# JIANGYA.net
KiCad netlist of a schematic drawn in Altium Designer
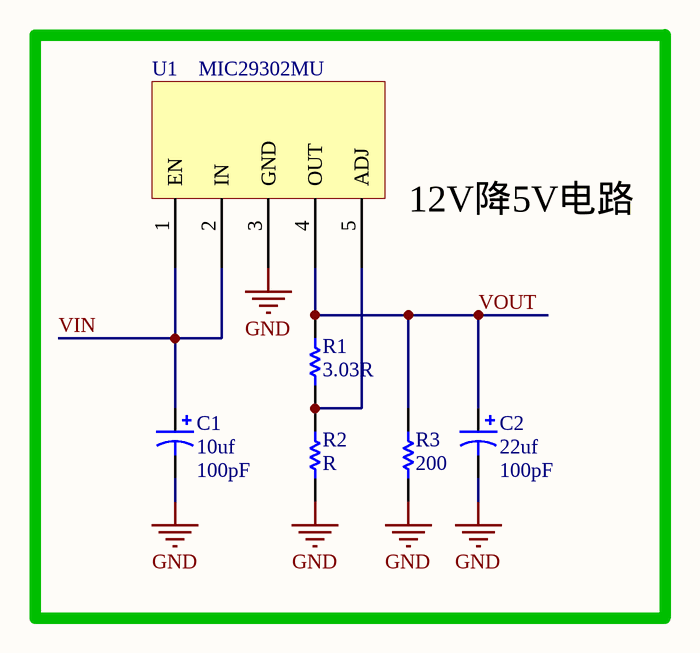
[diagram p0: JIANGYA.SchDoc]

(export (version "E")
  (design (tool "Eeschema 10.0.6"))
  (components
    (comp (ref "C1")
      (value "10uf")
      (footprint "RB7.6-15")
      (description "Polarized Capacitor (Radial)")
      (fields (field (name "ALTIUM_VALUE") "100pF") (field (name "PUBLISHER") "Altium Limited"))
      (libsource (lib "Miscellaneous Devices") (part "Cap Pol1"))
    )
    (comp (ref "C2")
      (value "22uf")
      (footprint "RB7.6-15")
      (description "Polarized Capacitor (Radial)")
      (fields (field (name "ALTIUM_VALUE") "100pF") (field (name "PUBLISHER") "Altium Limited"))
      (libsource (lib "Miscellaneous Devices") (part "Cap Pol1"))
    )
    (comp (ref "R1")
      (value "3.03R")
      (footprint "AXIAL-0.3")
      (description "Resistor")
      (fields (field (name "PUBLISHER") "Altium Limited"))
      (libsource (lib "Miscellaneous Devices") (part "Res1"))
    )
    (comp (ref "R2")
      (value "R")
      (footprint "AXIAL-0.3")
      (description "Resistor")
      (fields (field (name "PUBLISHER") "Altium Limited"))
      (libsource (lib "Miscellaneous Devices") (part "Res1"))
    )
    (comp (ref "R3")
      (value "200")
      (footprint "AXIAL-0.3")
      (description "Resistor")
      (fields (field (name "PUBLISHER") "Altium Limited"))
      (libsource (lib "Miscellaneous Devices") (part "Res1"))
    )
    (comp (ref "U1")
      (value "MIC29302MU")
      (footprint "TO263-5")
      (libsource (lib "TO263-5") (part "Component_1"))
    )
  )
  (nets
    (net (code "1") (name "/VIN") (class "Default")
      (node (ref "C1") (pin "1") (pinfunction "1_1") (pintype "passive"))
      (node (ref "U1") (pin "1") (pinfunction "EN_1") (pintype "passive"))
      (node (ref "U1") (pin "2") (pinfunction "IN_2") (pintype "passive"))
    )
    (net (code "2") (name "/VOUT") (class "Default")
      (node (ref "C2") (pin "1") (pinfunction "1_1") (pintype "passive"))
      (node (ref "R1") (pin "2") (pinfunction "2_2") (pintype "passive"))
      (node (ref "R3") (pin "2") (pinfunction "2_2") (pintype "passive"))
      (node (ref "U1") (pin "4") (pinfunction "OUT_4") (pintype "passive"))
    )
    (net (code "3") (name "GND") (class "Default")
      (node (ref "C1") (pin "2") (pinfunction "2_2") (pintype "passive"))
      (node (ref "C2") (pin "2") (pinfunction "2_2") (pintype "passive"))
      (node (ref "R2") (pin "1") (pinfunction "1_1") (pintype "passive"))
      (node (ref "R3") (pin "1") (pinfunction "1_1") (pintype "passive"))
      (node (ref "U1") (pin "3") (pinfunction "GND_3") (pintype "passive"))
    )
    (net (code "4") (name "Net-(U1-ADJ)") (class "Default")
      (node (ref "R1") (pin "1") (pinfunction "1_1") (pintype "passive"))
      (node (ref "R2") (pin "2") (pinfunction "2_2") (pintype "passive"))
      (node (ref "U1") (pin "5") (pinfunction "ADJ_5") (pintype "passive"))
    )
  )
)
